# PreampBoard.net
KiCad netlist of a schematic drawn in EAGLE
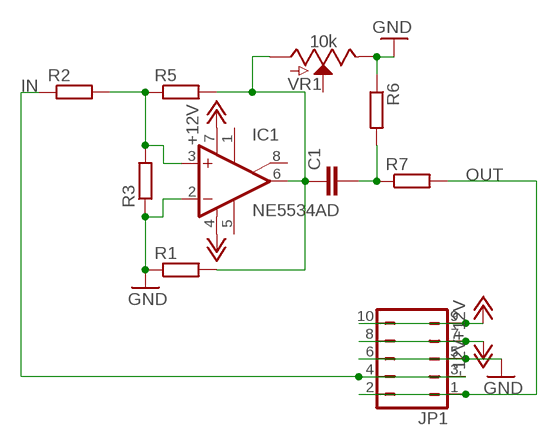
[diagram p0: schematic, sheet 1]

(export (version "E")
  (design (tool "Eeschema 10.0.6"))
  (components
    (comp (ref "C1")
      (value "C-EUC0805")
      (footprint "eagle-import:C0805")
      (libsource (lib "eagle-import") (part "C-EUC0805"))
    )
    (comp (ref "IC1")
      (value "NE5534AD")
      (footprint "eagle-import:SO08")
      (libsource (lib "eagle-import") (part "NE5534DA"))
    )
    (comp (ref "JP1")
      (value "JP5Q")
      (footprint "eagle-import:JP5Q")
      (libsource (lib "eagle-import") (part "JP5Q"))
    )
    (comp (ref "R1")
      (value "R-EU_R0805")
      (footprint "eagle-import:R0805")
      (libsource (lib "eagle-import") (part "R-EU_R0805"))
    )
    (comp (ref "R2")
      (value "R-EU_R0805")
      (footprint "eagle-import:R0805")
      (libsource (lib "eagle-import") (part "R-EU_R0805"))
    )
    (comp (ref "R3")
      (value "R-EU_R0805")
      (footprint "eagle-import:R0805")
      (libsource (lib "eagle-import") (part "R-EU_R0805"))
    )
    (comp (ref "R5")
      (value "R-EU_R0805")
      (footprint "eagle-import:R0805")
      (libsource (lib "eagle-import") (part "R-EU_R0805"))
    )
    (comp (ref "R6")
      (value "R-EU_R0805")
      (footprint "eagle-import:R0805")
      (libsource (lib "eagle-import") (part "R-EU_R0805"))
    )
    (comp (ref "R7")
      (value "R-EU_R0805")
      (footprint "eagle-import:R0805")
      (libsource (lib "eagle-import") (part "R-EU_R0805"))
    )
    (comp (ref "VR1")
      (value "10k")
      (footprint "eagle-import:POT-PTH-ALPS")
      (libsource (lib "eagle-import") (part "POTENTIOMETER-PTH-9MM-1/20W-20%"))
    )
  )
  (nets
    (net (code "1") (name "+12V") (class "Default")
      (node (ref "IC1") (pin "7") (pinfunction "V+_7") (pintype "power_in"))
      (node (ref "JP1") (pin "10") (pinfunction "10_10") (pintype "passive"))
      (node (ref "JP1") (pin "9") (pinfunction "9_9") (pintype "passive"))
    )
    (net (code "2") (name "-12V") (class "Default")
      (node (ref "IC1") (pin "4") (pinfunction "V-_4") (pintype "power_in"))
      (node (ref "JP1") (pin "7") (pinfunction "7_7") (pintype "passive"))
      (node (ref "JP1") (pin "8") (pinfunction "8_8") (pintype "passive"))
    )
    (net (code "3") (name "/IN") (class "Default")
      (node (ref "JP1") (pin "3") (pinfunction "3_3") (pintype "passive"))
      (node (ref "JP1") (pin "4") (pinfunction "4_4") (pintype "passive"))
      (node (ref "R2") (pin "1") (pinfunction "1_1") (pintype "passive"))
    )
    (net (code "4") (name "/OUT") (class "Default")
      (node (ref "JP1") (pin "1") (pinfunction "1_1") (pintype "passive"))
      (node (ref "JP1") (pin "2") (pinfunction "2_2") (pintype "passive"))
      (node (ref "R7") (pin "2") (pinfunction "2_2") (pintype "passive"))
    )
    (net (code "5") (name "GND") (class "Default")
      (node (ref "IC1") (pin "2") (pinfunction "-IN_2") (pintype "input"))
      (node (ref "JP1") (pin "5") (pinfunction "5_5") (pintype "passive"))
      (node (ref "JP1") (pin "6") (pinfunction "6_6") (pintype "passive"))
      (node (ref "R1") (pin "1") (pinfunction "1_1") (pintype "passive"))
      (node (ref "R3") (pin "1") (pinfunction "1_1") (pintype "passive"))
      (node (ref "R6") (pin "1") (pinfunction "1_1") (pintype "passive"))
      (node (ref "VR1") (pin "P$1") (pinfunction "E_P$1") (pintype "passive"))
    )
    (net (code "6") (name "Net-(C1-Pad2)") (class "Default")
      (node (ref "C1") (pin "2") (pinfunction "2_2") (pintype "passive"))
      (node (ref "R6") (pin "2") (pinfunction "2_2") (pintype "passive"))
      (node (ref "R7") (pin "1") (pinfunction "1_1") (pintype "passive"))
    )
    (net (code "7") (name "Net-(IC1-+IN)") (class "Default")
      (node (ref "IC1") (pin "3") (pinfunction "+IN_3") (pintype "input"))
      (node (ref "R2") (pin "2") (pinfunction "2_2") (pintype "passive"))
      (node (ref "R3") (pin "2") (pinfunction "2_2") (pintype "passive"))
      (node (ref "R5") (pin "1") (pinfunction "1_1") (pintype "passive"))
    )
    (net (code "8") (name "Net-(IC1-OUT)") (class "Default")
      (node (ref "C1") (pin "1") (pinfunction "1_1") (pintype "passive"))
      (node (ref "IC1") (pin "6") (pinfunction "OUT_6") (pintype "output"))
      (node (ref "R1") (pin "2") (pinfunction "2_2") (pintype "passive"))
      (node (ref "R5") (pin "2") (pinfunction "2_2") (pintype "passive"))
      (node (ref "VR1") (pin "P$3") (pinfunction "A_P$3") (pintype "passive"))
    )
    (net (code "9") (name "unconnected-(IC1-CMP-Pad5)") (class "Default")
      (node (ref "IC1") (pin "5") (pinfunction "CMP_5") (pintype "passive"))
    )
    (net (code "10") (name "unconnected-(IC1-ON-Pad1)") (class "Default")
      (node (ref "IC1") (pin "1") (pinfunction "ON_1") (pintype "passive"))
    )
    (net (code "11") (name "unconnected-(IC1-ON{slash}CMP-Pad8)") (class "Default")
      (node (ref "IC1") (pin "8") (pinfunction "ON/CMP_8") (pintype "passive"))
    )
    (net (code "12") (name "unconnected-(VR1-S-PadP$2)") (class "Default")
      (node (ref "VR1") (pin "P$2") (pinfunction "S_P$2") (pintype "passive"))
    )
  )
)
